# WagaGSM.net
KiCad netlist of a schematic drawn in EAGLE
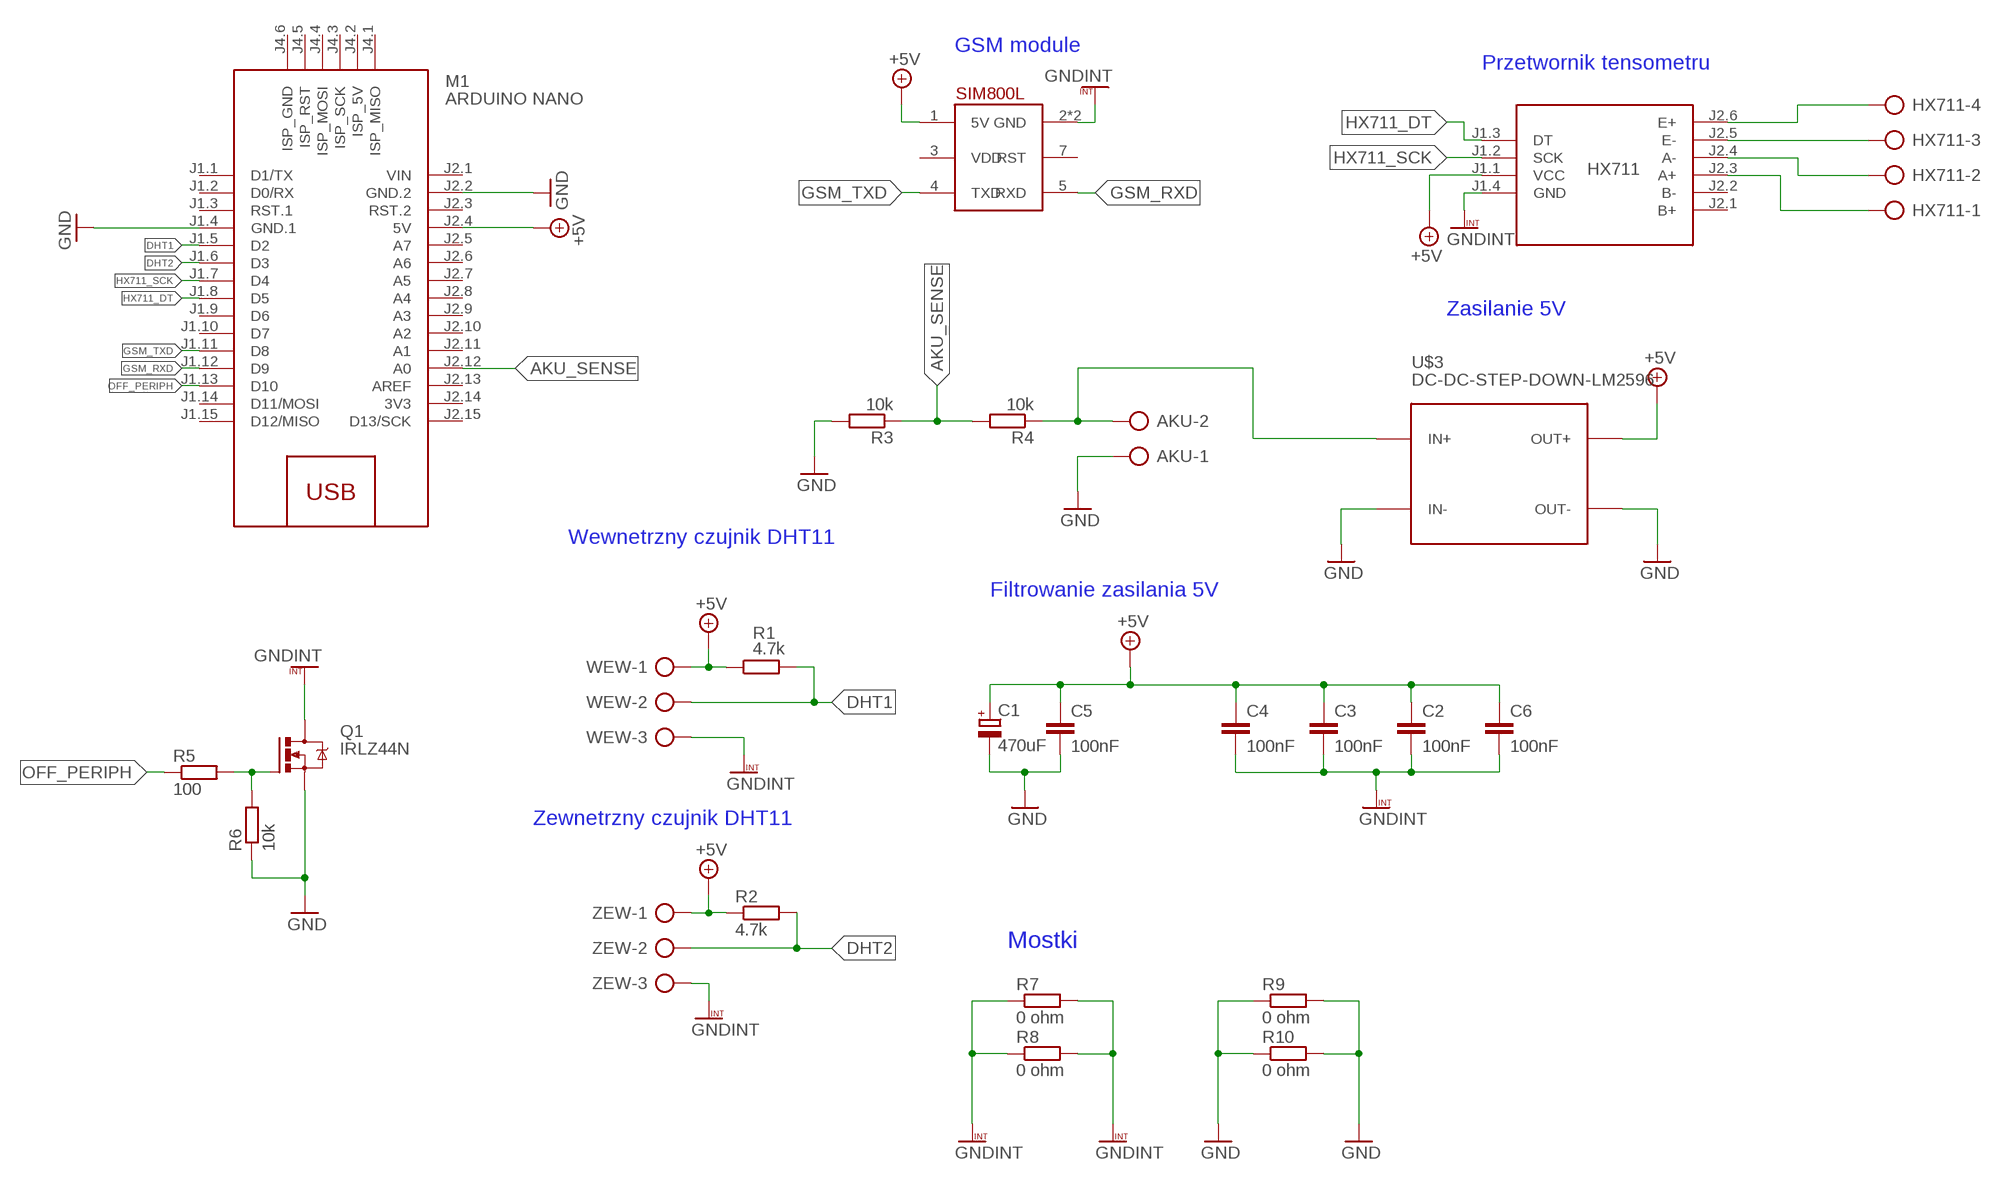
[diagram p0: schematic, sheet 1]

(export (version "E")
  (design (tool "Eeschema 10.0.6"))
  (components
    (comp (ref "AKU")
      (value "AK500/2-H")
      (footprint "eagle-import:AK500_2-H")
      (libsource (lib "eagle-import") (part "AK500/2-H"))
    )
    (comp (ref "C1")
      (value "470uF")
      (footprint "eagle-import:E5-10,5")
      (libsource (lib "eagle-import") (part "CPOL-EUE5-10.5"))
    )
    (comp (ref "C2")
      (value "100nF")
      (footprint "eagle-import:C050-030X075")
      (libsource (lib "eagle-import") (part "C-EU050-030X075"))
    )
    (comp (ref "C3")
      (value "100nF")
      (footprint "eagle-import:C050-030X075")
      (libsource (lib "eagle-import") (part "C-EU050-030X075"))
    )
    (comp (ref "C4")
      (value "100nF")
      (footprint "eagle-import:C050-030X075")
      (libsource (lib "eagle-import") (part "C-EU050-030X075"))
    )
    (comp (ref "C5")
      (value "100nF")
      (footprint "eagle-import:C050-030X075")
      (libsource (lib "eagle-import") (part "C-EU050-030X075"))
    )
    (comp (ref "C6")
      (value "100nF")
      (footprint "eagle-import:C050-030X075")
      (libsource (lib "eagle-import") (part "C-EU050-030X075"))
    )
    (comp (ref "HX711")
      (value "AK300/4")
      (footprint "eagle-import:AK300_4")
      (libsource (lib "eagle-import") (part "AK300/4"))
    )
    (comp (ref "M1")
      (value "ARDUINO NANO")
      (footprint "eagle-import:ARDUINO-NANO-3.0#ISP")
      (libsource (lib "eagle-import") (part "ARDUINO-NANO-3.0#ISP"))
    )
    (comp (ref "Q1")
      (value "IRLZ44N")
      (footprint "eagle-import:TO220BH")
      (libsource (lib "eagle-import") (part "IRFZ48Z"))
    )
    (comp (ref "R1")
      (value "4.7k")
      (footprint "eagle-import:0204_7")
      (libsource (lib "eagle-import") (part "R-EU_0204/7"))
    )
    (comp (ref "R2")
      (value "4.7k")
      (footprint "eagle-import:0204_7")
      (libsource (lib "eagle-import") (part "R-EU_0204/7"))
    )
    (comp (ref "R3")
      (value "10k")
      (footprint "eagle-import:0207_10")
      (libsource (lib "eagle-import") (part "R-EU_0207/10"))
    )
    (comp (ref "R4")
      (value "10k")
      (footprint "eagle-import:0207_10")
      (libsource (lib "eagle-import") (part "R-EU_0207/10"))
    )
    (comp (ref "R5")
      (value "100")
      (footprint "eagle-import:0207_7")
      (libsource (lib "eagle-import") (part "R-EU_0207/7"))
    )
    (comp (ref "R6")
      (value "10k")
      (footprint "eagle-import:0207_7")
      (libsource (lib "eagle-import") (part "R-EU_0207/7"))
    )
    (comp (ref "R7")
      (value "0 ohm")
      (footprint "eagle-import:0204_7")
      (libsource (lib "eagle-import") (part "R-EU_0204/7"))
    )
    (comp (ref "R8")
      (value "0 ohm")
      (footprint "eagle-import:0204_7")
      (libsource (lib "eagle-import") (part "R-EU_0204/7"))
    )
    (comp (ref "R9")
      (value "0 ohm")
      (footprint "eagle-import:0204_7")
      (libsource (lib "eagle-import") (part "R-EU_0204/7"))
    )
    (comp (ref "R10")
      (value "0 ohm")
      (footprint "eagle-import:0204_7")
      (libsource (lib "eagle-import") (part "R-EU_0204/7"))
    )
    (comp (ref "U$1")
      (value "SIM800L")
      (footprint "eagle-import:SIP")
      (libsource (lib "eagle-import") (part "SIM800L"))
    )
    (comp (ref "U$2")
      (value "HX711")
      (footprint "eagle-import:HX711")
      (libsource (lib "eagle-import") (part "HX711"))
    )
    (comp (ref "U$3")
      (value "DC-DC-STEP-DOWN-LM2596")
      (footprint "eagle-import:DC-DC-STEP-DOWN-LM2596")
      (libsource (lib "eagle-import") (part "DC-DC-STEP-DOWN-LM2596"))
    )
    (comp (ref "WEW")
      (value "AK500/3-H")
      (footprint "eagle-import:AK500_3-H")
      (libsource (lib "eagle-import") (part "AK500/3-H"))
    )
    (comp (ref "ZEW")
      (value "AK500/3-H")
      (footprint "eagle-import:AK500_3-H")
      (libsource (lib "eagle-import") (part "AK500/3-H"))
    )
  )
  (nets
    (net (code "1") (name "+5V") (class "Default")
      (node (ref "C1") (pin "+") (pinfunction "+_+") (pintype "passive"))
      (node (ref "C2") (pin "1") (pinfunction "1_1") (pintype "passive"))
      (node (ref "C3") (pin "1") (pinfunction "1_1") (pintype "passive"))
      (node (ref "C4") (pin "1") (pinfunction "1_1") (pintype "passive"))
      (node (ref "C5") (pin "1") (pinfunction "1_1") (pintype "passive"))
      (node (ref "C6") (pin "1") (pinfunction "1_1") (pintype "passive"))
      (node (ref "M1") (pin "J2.4") (pinfunction "5V_J2.4") (pintype "power_in"))
      (node (ref "R1") (pin "1") (pinfunction "1_1") (pintype "passive"))
      (node (ref "R2") (pin "1") (pinfunction "1_1") (pintype "passive"))
      (node (ref "U$1") (pin "1") (pinfunction "5V_1") (pintype "bidirectional"))
      (node (ref "U$2") (pin "J1.1") (pinfunction "VCC_J1.1") (pintype "power_in"))
      (node (ref "U$3") (pin "OUT+") (pinfunction "OUT+_OUT+") (pintype "bidirectional"))
      (node (ref "WEW") (pin "1") (pinfunction "KL_1") (pintype "passive"))
      (node (ref "ZEW") (pin "1") (pinfunction "KL_1") (pintype "passive"))
    )
    (net (code "2") (name "3V3") (class "Default")
      (node (ref "M1") (pin "J2.14") (pinfunction "3V3_J2.14") (pintype "power_in"))
    )
    (net (code "3") (name "AKU_SENSE") (class "Default")
      (node (ref "M1") (pin "J2.12") (pinfunction "A0_J2.12") (pintype "bidirectional"))
      (node (ref "R3") (pin "1") (pinfunction "1_1") (pintype "passive"))
      (node (ref "R4") (pin "2") (pinfunction "2_2") (pintype "passive"))
    )
    (net (code "4") (name "B-") (class "Default")
      (node (ref "U$2") (pin "J2.2") (pinfunction "B-_J2.2") (pintype "power_in"))
    )
    (net (code "5") (name "DHT1") (class "Default")
      (node (ref "M1") (pin "J1.5") (pinfunction "D2_J1.5") (pintype "bidirectional"))
      (node (ref "R1") (pin "2") (pinfunction "2_2") (pintype "passive"))
      (node (ref "WEW") (pin "2") (pinfunction "KL_2") (pintype "passive"))
    )
    (net (code "6") (name "DHT2") (class "Default")
      (node (ref "M1") (pin "J1.6") (pinfunction "D3_J1.6") (pintype "bidirectional"))
      (node (ref "R2") (pin "2") (pinfunction "2_2") (pintype "passive"))
      (node (ref "ZEW") (pin "2") (pinfunction "KL_2") (pintype "passive"))
    )
    (net (code "7") (name "GND") (class "Default")
      (node (ref "AKU") (pin "1") (pinfunction "KL_1") (pintype "passive"))
      (node (ref "C1") (pin "-") (pinfunction "-_-") (pintype "passive"))
      (node (ref "C5") (pin "2") (pinfunction "2_2") (pintype "passive"))
      (node (ref "M1") (pin "J1.4") (pinfunction "GND.1_J1.4") (pintype "power_in"))
      (node (ref "M1") (pin "J2.2") (pinfunction "GND.2_J2.2") (pintype "power_in"))
      (node (ref "Q1") (pin "S") (pinfunction "S_S") (pintype "passive"))
      (node (ref "R10") (pin "1") (pinfunction "1_1") (pintype "passive"))
      (node (ref "R10") (pin "2") (pinfunction "2_2") (pintype "passive"))
      (node (ref "R3") (pin "2") (pinfunction "2_2") (pintype "passive"))
      (node (ref "R6") (pin "1") (pinfunction "1_1") (pintype "passive"))
      (node (ref "R9") (pin "1") (pinfunction "1_1") (pintype "passive"))
      (node (ref "R9") (pin "2") (pinfunction "2_2") (pintype "passive"))
      (node (ref "U$3") (pin "IN-") (pinfunction "IN-_IN-") (pintype "bidirectional"))
      (node (ref "U$3") (pin "OUT-") (pinfunction "OUT-_OUT-") (pintype "bidirectional"))
    )
    (net (code "8") (name "GNDINT") (class "Default")
      (node (ref "C2") (pin "2") (pinfunction "2_2") (pintype "passive"))
      (node (ref "C3") (pin "2") (pinfunction "2_2") (pintype "passive"))
      (node (ref "C4") (pin "2") (pinfunction "2_2") (pintype "passive"))
      (node (ref "C6") (pin "2") (pinfunction "2_2") (pintype "passive"))
      (node (ref "Q1") (pin "D") (pinfunction "D_D") (pintype "passive"))
      (node (ref "R7") (pin "1") (pinfunction "1_1") (pintype "passive"))
      (node (ref "R7") (pin "2") (pinfunction "2_2") (pintype "passive"))
      (node (ref "R8") (pin "1") (pinfunction "1_1") (pintype "passive"))
      (node (ref "R8") (pin "2") (pinfunction "2_2") (pintype "passive"))
      (node (ref "U$1") (pin "2") (pinfunction "GND_2") (pintype "bidirectional"))
      (node (ref "U$1") (pin "6") (pinfunction "GND_6") (pintype "bidirectional"))
      (node (ref "U$2") (pin "J1.4") (pinfunction "GND_J1.4") (pintype "power_in"))
      (node (ref "WEW") (pin "3") (pinfunction "KL_3") (pintype "passive"))
      (node (ref "ZEW") (pin "3") (pinfunction "KL_3") (pintype "passive"))
    )
    (net (code "9") (name "GSM_RXD") (class "Default")
      (node (ref "M1") (pin "J1.12") (pinfunction "D9_J1.12") (pintype "bidirectional"))
      (node (ref "U$1") (pin "5") (pinfunction "RXD_5") (pintype "bidirectional"))
    )
    (net (code "10") (name "GSM_TXD") (class "Default")
      (node (ref "M1") (pin "J1.11") (pinfunction "D8_J1.11") (pintype "bidirectional"))
      (node (ref "U$1") (pin "4") (pinfunction "TXD_4") (pintype "bidirectional"))
    )
    (net (code "11") (name "HX711_DT") (class "Default")
      (node (ref "M1") (pin "J1.8") (pinfunction "D5_J1.8") (pintype "bidirectional"))
      (node (ref "U$2") (pin "J1.3") (pinfunction "DT_J1.3") (pintype "bidirectional"))
    )
    (net (code "12") (name "HX711_SCK") (class "Default")
      (node (ref "M1") (pin "J1.7") (pinfunction "D4_J1.7") (pintype "bidirectional"))
      (node (ref "U$2") (pin "J1.2") (pinfunction "SCK_J1.2") (pintype "bidirectional"))
    )
    (net (code "13") (name "Net-(AKUB-KL)") (class "Default")
      (node (ref "AKU") (pin "2") (pinfunction "KL_2") (pintype "passive"))
      (node (ref "R4") (pin "1") (pinfunction "1_1") (pintype "passive"))
      (node (ref "U$3") (pin "IN+") (pinfunction "IN+_IN+") (pintype "bidirectional"))
    )
    (net (code "14") (name "Net-(HX711A-KL)") (class "Default")
      (node (ref "HX711") (pin "1") (pinfunction "KL_1") (pintype "passive"))
      (node (ref "U$2") (pin "J2.3") (pinfunction "A+_J2.3") (pintype "power_in"))
    )
    (net (code "15") (name "Net-(HX711B-KL)") (class "Default")
      (node (ref "HX711") (pin "2") (pinfunction "KL_2") (pintype "passive"))
      (node (ref "U$2") (pin "J2.4") (pinfunction "A-_J2.4") (pintype "bidirectional"))
    )
    (net (code "16") (name "Net-(HX711C-KL)") (class "Default")
      (node (ref "HX711") (pin "3") (pinfunction "KL_3") (pintype "passive"))
      (node (ref "U$2") (pin "J2.5") (pinfunction "E-_J2.5") (pintype "bidirectional"))
    )
    (net (code "17") (name "Net-(HX711D-KL)") (class "Default")
      (node (ref "HX711") (pin "4") (pinfunction "KL_4") (pintype "passive"))
      (node (ref "U$2") (pin "J2.6") (pinfunction "E+_J2.6") (pintype "bidirectional"))
    )
    (net (code "18") (name "Net-(Q1-PadG)") (class "Default")
      (node (ref "Q1") (pin "G") (pinfunction "G_G") (pintype "passive"))
      (node (ref "R5") (pin "2") (pinfunction "2_2") (pintype "passive"))
      (node (ref "R6") (pin "2") (pinfunction "2_2") (pintype "passive"))
    )
    (net (code "19") (name "OFF_PERIPH") (class "Default")
      (node (ref "M1") (pin "J1.13") (pinfunction "D10_J1.13") (pintype "bidirectional"))
      (node (ref "R5") (pin "1") (pinfunction "1_1") (pintype "passive"))
    )
    (net (code "20") (name "VIN") (class "Default")
      (node (ref "M1") (pin "J2.1") (pinfunction "VIN_J2.1") (pintype "power_in"))
    )
    (net (code "21") (name "unconnected-(M1-A1-PadJ2.11)") (class "Default")
      (node (ref "M1") (pin "J2.11") (pinfunction "A1_J2.11") (pintype "bidirectional"))
    )
    (net (code "22") (name "unconnected-(M1-A2-PadJ2.10)") (class "Default")
      (node (ref "M1") (pin "J2.10") (pinfunction "A2_J2.10") (pintype "bidirectional"))
    )
    (net (code "23") (name "unconnected-(M1-A3-PadJ2.9)") (class "Default")
      (node (ref "M1") (pin "J2.9") (pinfunction "A3_J2.9") (pintype "bidirectional"))
    )
    (net (code "24") (name "unconnected-(M1-A4-PadJ2.8)") (class "Default")
      (node (ref "M1") (pin "J2.8") (pinfunction "A4_J2.8") (pintype "bidirectional"))
    )
    (net (code "25") (name "unconnected-(M1-A5-PadJ2.7)") (class "Default")
      (node (ref "M1") (pin "J2.7") (pinfunction "A5_J2.7") (pintype "bidirectional"))
    )
    (net (code "26") (name "unconnected-(M1-A6-PadJ2.6)") (class "Default")
      (node (ref "M1") (pin "J2.6") (pinfunction "A6_J2.6") (pintype "bidirectional"))
    )
    (net (code "27") (name "unconnected-(M1-A7-PadJ2.5)") (class "Default")
      (node (ref "M1") (pin "J2.5") (pinfunction "A7_J2.5") (pintype "bidirectional"))
    )
    (net (code "28") (name "unconnected-(M1-AREF-PadJ2.13)") (class "Default")
      (node (ref "M1") (pin "J2.13") (pinfunction "AREF_J2.13") (pintype "bidirectional"))
    )
    (net (code "29") (name "unconnected-(M1-D0{slash}RX-PadJ1.2)") (class "Default")
      (node (ref "M1") (pin "J1.2") (pinfunction "D0/RX_J1.2") (pintype "bidirectional"))
    )
    (net (code "30") (name "unconnected-(M1-D1{slash}TX-PadJ1.1)") (class "Default")
      (node (ref "M1") (pin "J1.1") (pinfunction "D1/TX_J1.1") (pintype "bidirectional"))
    )
    (net (code "31") (name "unconnected-(M1-D6-PadJ1.9)") (class "Default")
      (node (ref "M1") (pin "J1.9") (pinfunction "D6_J1.9") (pintype "bidirectional"))
    )
    (net (code "32") (name "unconnected-(M1-D7-PadJ1.10)") (class "Default")
      (node (ref "M1") (pin "J1.10") (pinfunction "D7_J1.10") (pintype "bidirectional"))
    )
    (net (code "33") (name "unconnected-(M1-D11{slash}MOSI-PadJ1.14)") (class "Default")
      (node (ref "M1") (pin "J1.14") (pinfunction "D11/MOSI_J1.14") (pintype "bidirectional"))
    )
    (net (code "34") (name "unconnected-(M1-D12{slash}MISO-PadJ1.15)") (class "Default")
      (node (ref "M1") (pin "J1.15") (pinfunction "D12/MISO_J1.15") (pintype "bidirectional"))
    )
    (net (code "35") (name "unconnected-(M1-D13{slash}SCK-PadJ2.15)") (class "Default")
      (node (ref "M1") (pin "J2.15") (pinfunction "D13/SCK_J2.15") (pintype "bidirectional"))
    )
    (net (code "36") (name "unconnected-(M1-ISP_5V-PadJ4.2)") (class "Default")
      (node (ref "M1") (pin "J4.2") (pinfunction "ISP_5V_J4.2") (pintype "bidirectional"))
    )
    (net (code "37") (name "unconnected-(M1-ISP_GND-PadJ4.6)") (class "Default")
      (node (ref "M1") (pin "J4.6") (pinfunction "ISP_GND_J4.6") (pintype "bidirectional"))
    )
    (net (code "38") (name "unconnected-(M1-ISP_MISO-PadJ4.1)") (class "Default")
      (node (ref "M1") (pin "J4.1") (pinfunction "ISP_MISO_J4.1") (pintype "bidirectional"))
    )
    (net (code "39") (name "unconnected-(M1-ISP_MOSI-PadJ4.4)") (class "Default")
      (node (ref "M1") (pin "J4.4") (pinfunction "ISP_MOSI_J4.4") (pintype "bidirectional"))
    )
    (net (code "40") (name "unconnected-(M1-ISP_RST-PadJ4.5)") (class "Default")
      (node (ref "M1") (pin "J4.5") (pinfunction "ISP_RST_J4.5") (pintype "bidirectional"))
    )
    (net (code "41") (name "unconnected-(M1-ISP_SCK-PadJ4.3)") (class "Default")
      (node (ref "M1") (pin "J4.3") (pinfunction "ISP_SCK_J4.3") (pintype "bidirectional"))
    )
    (net (code "42") (name "unconnected-(M1-RST.1-PadJ1.3)") (class "Default")
      (node (ref "M1") (pin "J1.3") (pinfunction "RST.1_J1.3") (pintype "bidirectional"))
    )
    (net (code "43") (name "unconnected-(M1-RST.2-PadJ2.3)") (class "Default")
      (node (ref "M1") (pin "J2.3") (pinfunction "RST.2_J2.3") (pintype "bidirectional"))
    )
    (net (code "44") (name "unconnected-(U$1-RST-Pad7)") (class "Default")
      (node (ref "U$1") (pin "7") (pinfunction "RST_7") (pintype "bidirectional"))
    )
    (net (code "45") (name "unconnected-(U$1-VDD-Pad3)") (class "Default")
      (node (ref "U$1") (pin "3") (pinfunction "VDD_3") (pintype "bidirectional"))
    )
    (net (code "46") (name "unconnected-(U$2-B+-PadJ2.1)") (class "Default")
      (node (ref "U$2") (pin "J2.1") (pinfunction "B+_J2.1") (pintype "bidirectional"))
    )
  )
)
